# Amplificador_Clase_D.net
KiCad netlist of a schematic drawn in Altium Designer
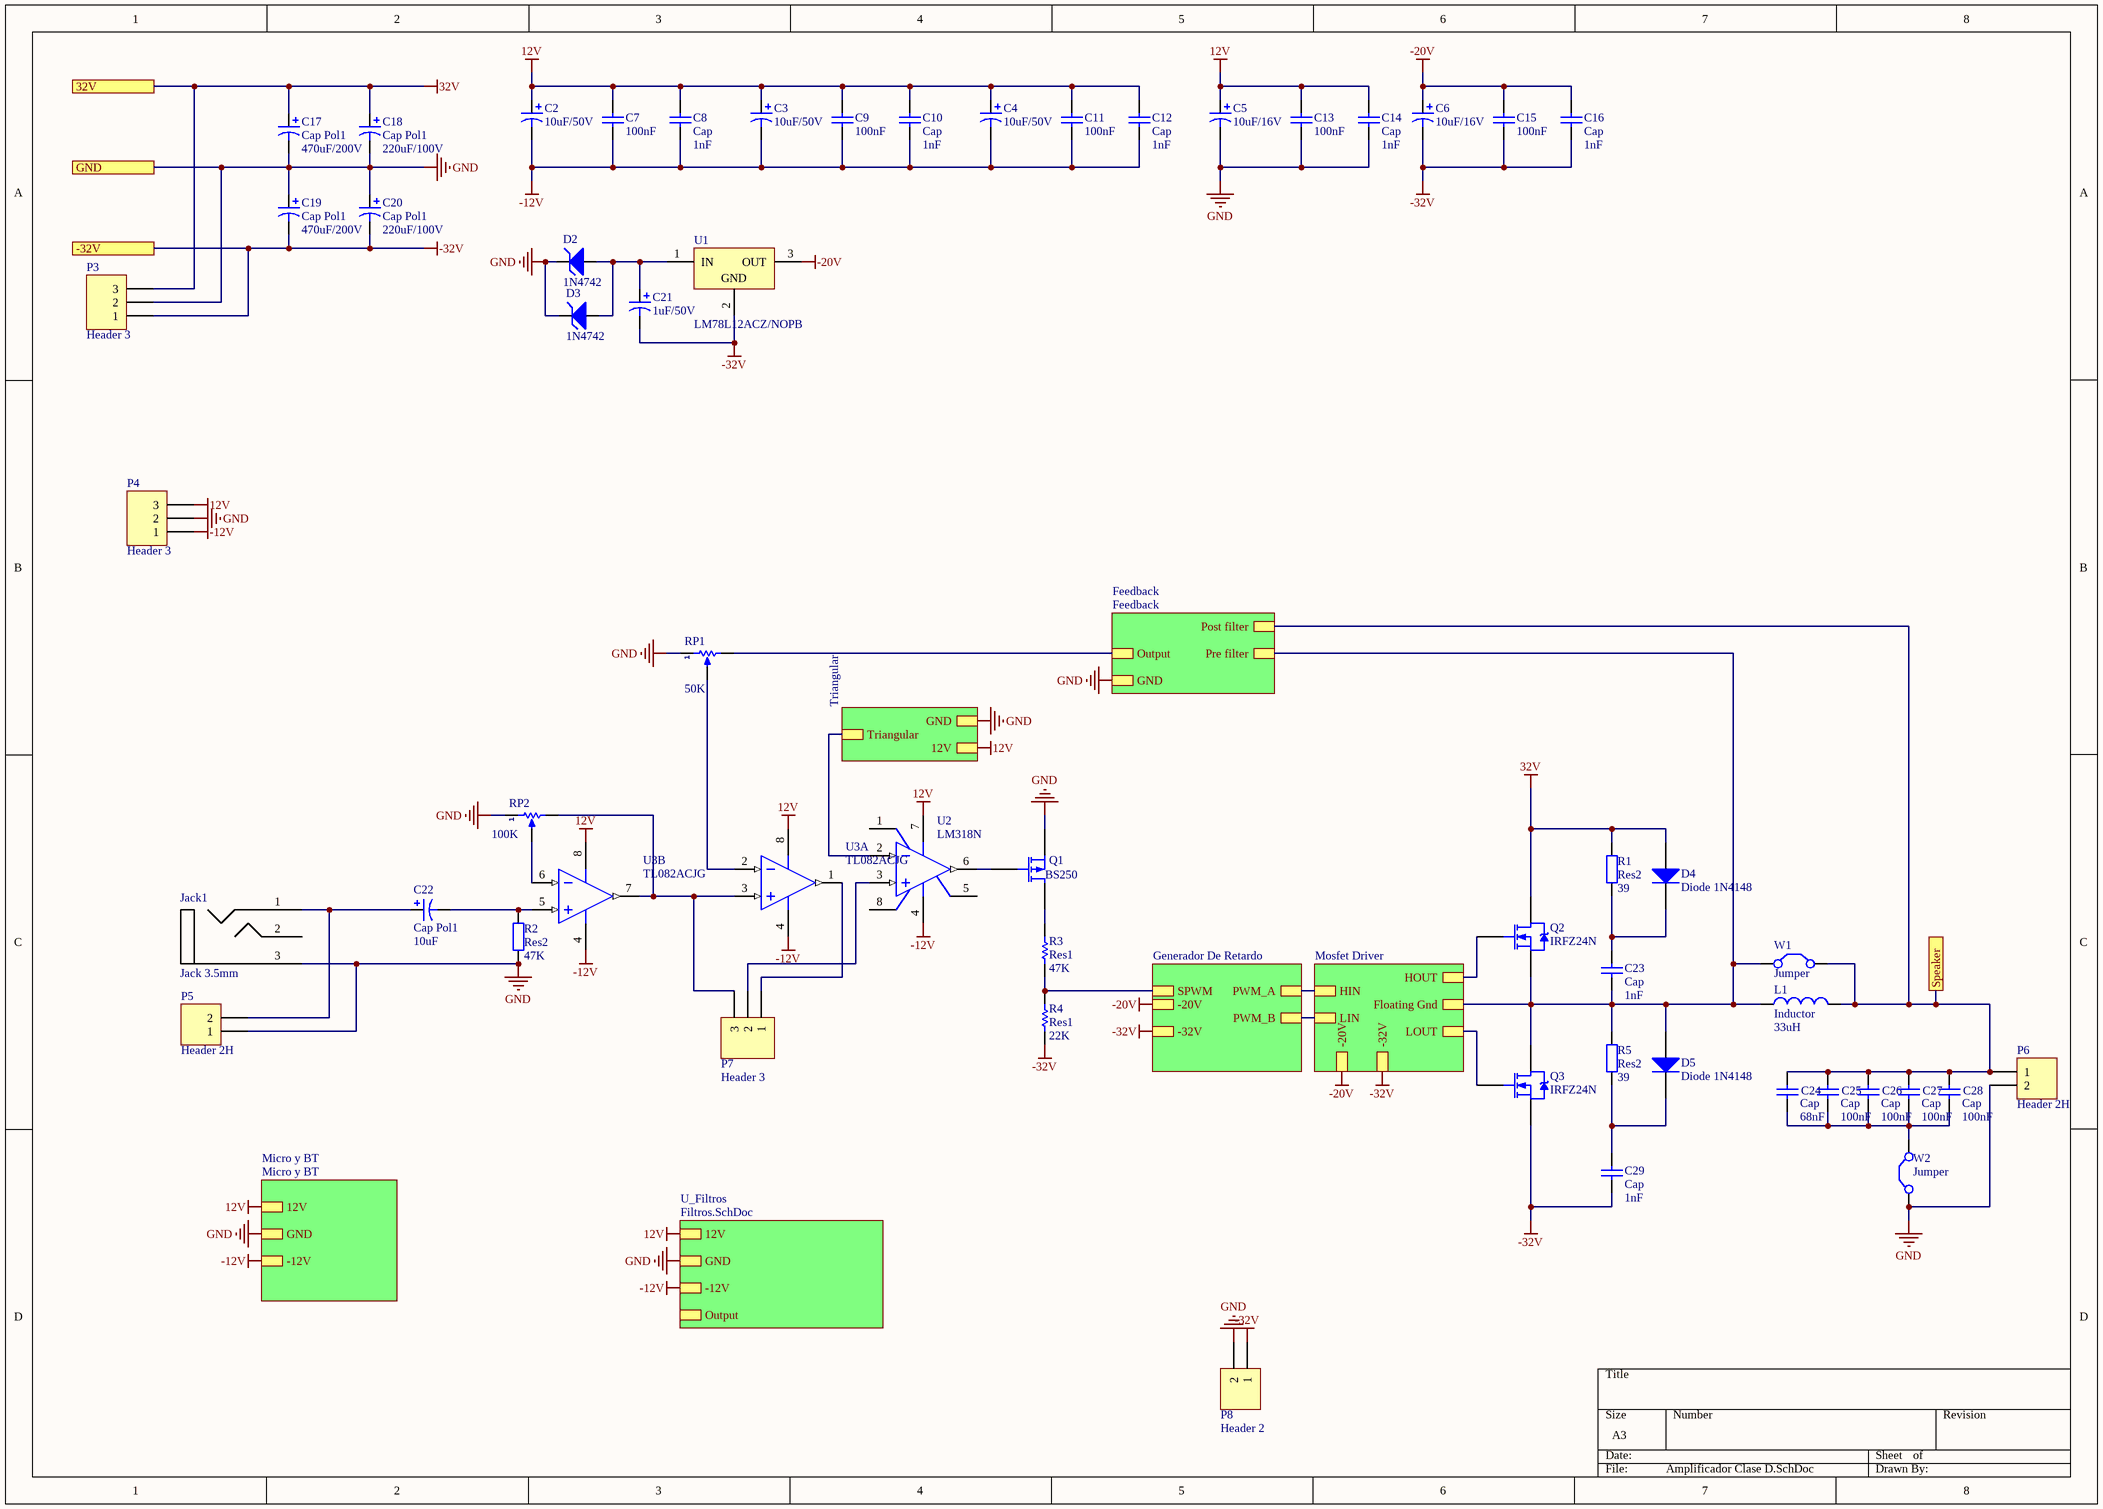
[diagram p0: Amplificador Clase D.SchDoc]

(export (version "E")
  (design (tool "Eeschema 10.0.6"))
  (components
    (comp (ref "C2")
      (value "Cap Electrolitico Radial")
      (footprint "CAPR D250 H450 R100 mil")
      (description "Cap Electrolitico de insercion")
      (fields (field (name "VALOR") "10uF/50V"))
      (libsource (lib "RUF-Dispositivos-Grales") (part "Cap Electrolitico Radial"))
    )
    (comp (ref "C3")
      (value "Cap Electrolitico Radial")
      (footprint "CAPR D250 H450 R100 mil")
      (description "Cap Electrolitico de insercion")
      (fields (field (name "VALOR") "10uF/50V"))
      (libsource (lib "RUF-Dispositivos-Grales") (part "Cap Electrolitico Radial"))
    )
    (comp (ref "C4")
      (value "Cap Electrolitico Radial")
      (footprint "CAPR D250 H450 R100 mil")
      (description "Cap Electrolitico de insercion")
      (fields (field (name "VALOR") "10uF/50V"))
      (libsource (lib "RUF-Dispositivos-Grales") (part "Cap Electrolitico Radial"))
    )
    (comp (ref "C5")
      (value "Cap Electrolitico Radial")
      (footprint "CAPR D250 H450 R100 mil")
      (description "Cap Electrolitico de insercion")
      (fields (field (name "VALOR") "10uF/16V"))
      (libsource (lib "RUF-Dispositivos-Grales") (part "Cap Electrolitico Radial"))
    )
    (comp (ref "C6")
      (value "Cap Electrolitico Radial")
      (footprint "CAPR D250 H450 R100 mil")
      (description "Cap Electrolitico de insercion")
      (fields (field (name "VALOR") "10uF/16V"))
      (libsource (lib "RUF-Dispositivos-Grales") (part "Cap Electrolitico Radial"))
    )
    (comp (ref "C7")
      (value "Cap Ceramico Disco")
      (footprint "RAD-0.3")
      (description "Capacitor Ceramico de Insercion")
      (fields (field (name "VALOR") "100nF"))
      (libsource (lib "RUF-Dispositivos-Grales") (part "Cap Ceramico Disco"))
    )
    (comp (ref "C8")
      (value "Cap")
      (footprint "CAP DISCO 200mil")
      (description "Capacitor")
      (fields (field (name "ALTIUM_VALUE") "1nF") (field (name "PUBLISHER") "Altium Limited"))
      (libsource (lib "Miscellaneous Devices") (part "Cap"))
    )
    (comp (ref "C9")
      (value "Cap Ceramico Disco")
      (footprint "RAD-0.3")
      (description "Capacitor Ceramico de Insercion")
      (fields (field (name "VALOR") "100nF"))
      (libsource (lib "RUF-Dispositivos-Grales") (part "Cap Ceramico Disco"))
    )
    (comp (ref "C10")
      (value "Cap")
      (footprint "CAP DISCO 200mil")
      (description "Capacitor")
      (fields (field (name "ALTIUM_VALUE") "1nF") (field (name "PUBLISHER") "Altium Limited"))
      (libsource (lib "Miscellaneous Devices") (part "Cap"))
    )
    (comp (ref "C11")
      (value "Cap Ceramico Disco")
      (footprint "RAD-0.3")
      (description "Capacitor Ceramico de Insercion")
      (fields (field (name "VALOR") "100nF"))
      (libsource (lib "RUF-Dispositivos-Grales") (part "Cap Ceramico Disco"))
    )
    (comp (ref "C12")
      (value "Cap")
      (footprint "CAP DISCO 200mil")
      (description "Capacitor")
      (fields (field (name "ALTIUM_VALUE") "1nF") (field (name "PUBLISHER") "Altium Limited"))
      (libsource (lib "Miscellaneous Devices") (part "Cap"))
    )
    (comp (ref "C13")
      (value "Cap Ceramico Disco")
      (footprint "RAD-0.3")
      (description "Capacitor Ceramico de Insercion")
      (fields (field (name "VALOR") "100nF"))
      (libsource (lib "RUF-Dispositivos-Grales") (part "Cap Ceramico Disco"))
    )
    (comp (ref "C14")
      (value "Cap")
      (footprint "CAP DISCO 200mil")
      (description "Capacitor")
      (fields (field (name "ALTIUM_VALUE") "1nF") (field (name "PUBLISHER") "Altium Limited"))
      (libsource (lib "Miscellaneous Devices") (part "Cap"))
    )
    (comp (ref "C15")
      (value "Cap Ceramico Disco")
      (footprint "RAD-0.3")
      (description "Capacitor Ceramico de Insercion")
      (fields (field (name "VALOR") "100nF"))
      (libsource (lib "RUF-Dispositivos-Grales") (part "Cap Ceramico Disco"))
    )
    (comp (ref "C16")
      (value "Cap")
      (footprint "CAP DISCO 200mil")
      (description "Capacitor")
      (fields (field (name "ALTIUM_VALUE") "1nF") (field (name "PUBLISHER") "Altium Limited"))
      (libsource (lib "Miscellaneous Devices") (part "Cap"))
    )
    (comp (ref "C17")
      (value "Cap Pol1")
      (footprint "CAPR D700 H1400 R300 mil")
      (description "Polarized Capacitor (Radial)")
      (fields (field (name "ALTIUM_VALUE") "470uF/200V") (field (name "PUBLISHER") "Altium Limited"))
      (libsource (lib "Miscellaneous Devices") (part "Cap Pol1"))
    )
    (comp (ref "C18")
      (value "Cap Pol1")
      (footprint "CAPR D500 H1000 R200 mil")
      (description "Polarized Capacitor (Radial)")
      (fields (field (name "ALTIUM_VALUE") "220uF/100V") (field (name "PUBLISHER") "Altium Limited"))
      (libsource (lib "Miscellaneous Devices") (part "Cap Pol1"))
    )
    (comp (ref "C19")
      (value "Cap Pol1")
      (footprint "CAPR D700 H1400 R300 mil")
      (description "Polarized Capacitor (Radial)")
      (fields (field (name "ALTIUM_VALUE") "470uF/200V") (field (name "PUBLISHER") "Altium Limited"))
      (libsource (lib "Miscellaneous Devices") (part "Cap Pol1"))
    )
    (comp (ref "C20")
      (value "Cap Pol1")
      (footprint "CAPR D500 H1000 R200 mil")
      (description "Polarized Capacitor (Radial)")
      (fields (field (name "ALTIUM_VALUE") "220uF/100V") (field (name "PUBLISHER") "Altium Limited"))
      (libsource (lib "Miscellaneous Devices") (part "Cap Pol1"))
    )
    (comp (ref "C21")
      (value "Cap Electrolitico Radial")
      (footprint "CAPR D250 H450 R100 mil")
      (description "Cap Electrolitico de insercion")
      (fields (field (name "VALOR") "1uF/50V"))
      (libsource (lib "RUF-Dispositivos-Grales") (part "Cap Electrolitico Radial"))
    )
    (comp (ref "C22")
      (value "Cap Pol1")
      (footprint "CAPR D250 H450 R100 mil")
      (description "Polarized Capacitor (Radial)")
      (fields (field (name "ALTIUM_VALUE") "10uF") (field (name "PUBLISHER") "Altium Limited"))
      (libsource (lib "Miscellaneous Devices") (part "Cap Pol1"))
    )
    (comp (ref "C23")
      (value "Cap")
      (footprint "CAP DISCO 200mil")
      (description "Capacitor")
      (fields (field (name "ALTIUM_VALUE") "1nF") (field (name "PUBLISHER") "Altium Limited"))
      (libsource (lib "Miscellaneous Devices") (part "Cap"))
    )
    (comp (ref "C24")
      (value "Cap")
      (footprint "RAD-0.4")
      (description "Capacitor")
      (fields (field (name "ALTIUM_VALUE") "68nF") (field (name "PUBLISHER") "Altium Limited"))
      (libsource (lib "Miscellaneous Devices") (part "Cap"))
    )
    (comp (ref "C25")
      (value "Cap")
      (footprint "RAD-0.4")
      (description "Capacitor")
      (fields (field (name "ALTIUM_VALUE") "100nF") (field (name "PUBLISHER") "Altium Limited"))
      (libsource (lib "Miscellaneous Devices") (part "Cap"))
    )
    (comp (ref "C26")
      (value "Cap")
      (footprint "RAD-0.4")
      (description "Capacitor")
      (fields (field (name "ALTIUM_VALUE") "100nF") (field (name "PUBLISHER") "Altium Limited"))
      (libsource (lib "Miscellaneous Devices") (part "Cap"))
    )
    (comp (ref "C27")
      (value "Cap")
      (footprint "RAD-0.4")
      (description "Capacitor")
      (fields (field (name "ALTIUM_VALUE") "100nF") (field (name "PUBLISHER") "Altium Limited"))
      (libsource (lib "Miscellaneous Devices") (part "Cap"))
    )
    (comp (ref "C28")
      (value "Cap")
      (footprint "RAD-0.4")
      (description "Capacitor")
      (fields (field (name "ALTIUM_VALUE") "100nF") (field (name "PUBLISHER") "Altium Limited"))
      (libsource (lib "Miscellaneous Devices") (part "Cap"))
    )
    (comp (ref "C29")
      (value "Cap")
      (footprint "CAP DISCO 200mil")
      (description "Capacitor")
      (fields (field (name "ALTIUM_VALUE") "1nF") (field (name "PUBLISHER") "Altium Limited"))
      (libsource (lib "Miscellaneous Devices") (part "Cap"))
    )
    (comp (ref "D2")
      (value "Diodo Zener")
      (footprint "DO-41")
      (fields (field (name "VALOR") "1N4742"))
      (libsource (lib "RUF-Dispositivos-Grales") (part "Diodo Zener"))
    )
    (comp (ref "D3")
      (value "Diodo Zener")
      (footprint "DO-41")
      (fields (field (name "VALOR") "1N4742"))
      (libsource (lib "RUF-Dispositivos-Grales") (part "Diodo Zener"))
    )
    (comp (ref "D4")
      (value "Diode 1N4148")
      (footprint "DO-41")
      (description "High Conductance Fast Diode")
      (fields (field (name "PUBLISHER") "Altium Limited"))
      (libsource (lib "Miscellaneous Devices") (part "Diode 1N4148"))
    )
    (comp (ref "D5")
      (value "Diode 1N4148")
      (footprint "DO-41")
      (description "High Conductance Fast Diode")
      (fields (field (name "PUBLISHER") "Altium Limited"))
      (libsource (lib "Miscellaneous Devices") (part "Diode 1N4148"))
    )
    (comp (ref "Jack1")
      (value "Jack 3.5mm")
      (footprint "jack 3.5mm")
      (libsource (lib "XR2206") (part "Jack 3.5mm"))
    )
    (comp (ref "L1")
      (value "Inductor")
      (footprint "Bobina 1.5*3")
      (fields (field (name "ALTIUM_VALUE") "33uH") (field (name "PUBLISHER") "Altium Limited"))
      (libsource (lib "Miscellaneous Devices") (part "Inductor"))
    )
    (comp (ref "P3")
      (value "Header 3")
      (footprint "bornera 3")
      (description "Header, 3-Pin")
      (fields (field (name "PUBLISHER") "Altium Limited"))
      (libsource (lib "Miscellaneous Connectors") (part "Header 3"))
    )
    (comp (ref "P4")
      (value "Header 3")
      (footprint "bornera 3")
      (description "Header, 3-Pin")
      (fields (field (name "PUBLISHER") "Altium Limited"))
      (libsource (lib "Miscellaneous Connectors") (part "Header 3"))
    )
    (comp (ref "P5")
      (value "Header 2H")
      (footprint "bornera 2")
      (description "Header, 2-Pin, Right Angle")
      (fields (field (name "PUBLISHER") "Altium Limited"))
      (libsource (lib "") (part "Header 2H_1"))
    )
    (comp (ref "P6")
      (value "Header 2H")
      (footprint "bornera 2")
      (description "Header, 2-Pin, Right Angle")
      (fields (field (name "PUBLISHER") "Altium Limited"))
      (libsource (lib "Miscellaneous Connectors") (part "Header 2H"))
    )
    (comp (ref "P7")
      (value "Header 3")
      (footprint "HDR1X3")
      (description "Header, 3-Pin")
      (fields (field (name "PUBLISHER") "Altium Limited"))
      (libsource (lib "") (part "Header 3_1"))
    )
    (comp (ref "P8")
      (value "Header 2")
      (footprint "HDR1X2")
      (description "Header, 2-Pin")
      (fields (field (name "PUBLISHER") "Altium Limited"))
      (libsource (lib "Miscellaneous Connectors") (part "Header 2"))
    )
    (comp (ref "Q1")
      (value "BS250")
      (footprint "TO-92W")
      (description "P-Channel MOSFET")
      (fields (field (name "PUBLISHER") "Altium Limited"))
      (libsource (lib "Miscellaneous Devices") (part "MOSFET-P"))
    )
    (comp (ref "Q2")
      (value "IRFZ24N")
      (footprint "TO-220AB")
      (description "HEXFET Power MOSFET")
      (fields (field (name "PUBLISHER") "Altium Limited"))
      (libsource (lib "IR Discrete MOSFET - Power") (part "IRFZ24N"))
    )
    (comp (ref "Q3")
      (value "IRFZ24N")
      (footprint "TO-220AB")
      (description "HEXFET Power MOSFET")
      (fields (field (name "PUBLISHER") "Altium Limited"))
      (libsource (lib "IR Discrete MOSFET - Power") (part "IRFZ24N"))
    )
    (comp (ref "R1")
      (value "Res2")
      (footprint "AXIAL-0.4")
      (description "Resistor")
      (fields (field (name "ALTIUM_VALUE") "39") (field (name "PUBLISHER") "Altium Limited"))
      (libsource (lib "Miscellaneous Devices") (part "Res2"))
    )
    (comp (ref "R2")
      (value "Res2")
      (footprint "1206 resistor")
      (description "Resistor")
      (fields (field (name "ALTIUM_VALUE") "47K") (field (name "PUBLISHER") "Altium Limited"))
      (libsource (lib "Miscellaneous Devices") (part "Res2"))
    )
    (comp (ref "R3")
      (value "Res1")
      (footprint "1206 resistor")
      (description "Resistor")
      (fields (field (name "ALTIUM_VALUE") "47K") (field (name "PUBLISHER") "Altium Limited"))
      (libsource (lib "Miscellaneous Devices") (part "Res1"))
    )
    (comp (ref "R4")
      (value "Res1")
      (footprint "1206 resistor")
      (description "Resistor")
      (fields (field (name "ALTIUM_VALUE") "22K") (field (name "PUBLISHER") "Altium Limited"))
      (libsource (lib "Miscellaneous Devices") (part "Res1"))
    )
    (comp (ref "R5")
      (value "Res2")
      (footprint "AXIAL-0.4")
      (description "Resistor")
      (fields (field (name "ALTIUM_VALUE") "39") (field (name "PUBLISHER") "Altium Limited"))
      (libsource (lib "Miscellaneous Devices") (part "Res2"))
    )
    (comp (ref "RP1")
      (value "Trimpot")
      (footprint "Trimpot Multivuelta Vertical")
      (description "Preset")
      (fields (field (name "VALOR") "50K"))
      (libsource (lib "RUF-Dispositivos-Grales") (part "Trimpot"))
    )
    (comp (ref "RP2")
      (value "Trimpot")
      (footprint "Trimpot Multivuelta Vertical")
      (description "Preset")
      (fields (field (name "VALOR") "100K"))
      (libsource (lib "RUF-Dispositivos-Grales") (part "Trimpot"))
    )
    (comp (ref "U1")
      (value "LM78L12ACZ/NOPB")
      (footprint "to-220")
      (description "3-Terminal Positive Regulators, 3-pin TO-92, Pb-Free")
      (fields
        (field (name "MANUFACTURER") "National Semiconductor")
        (field (name "PUBLISHER") "Altium Limited")
      )
      (libsource (lib "NSC LDO") (part "LM78L12ACZ/NOPB"))
    )
    (comp (ref "U2")
      (value "LM318N")
      (footprint "DIP-8")
      (description "Operational Amplifier, 8-pin MDIP")
      (fields
        (field (name "MANUFACTURER") "National Semiconductor")
        (field (name "PUBLISHER") "Altium Limited")
      )
      (libsource (lib "NSC Amplifier") (part "LM318N"))
    )
    (comp (ref "U3")
      (value "TL082ACJG")
      (footprint "693-02")
      (description "JFET-Input Operational Amplifier")
      (fields (field (name "PUBLISHER") "Altium Limited"))
      (libsource (lib "Motorola Amplifier Operational Amplifier") (part "TL082ACJG"))
    )
    (comp (ref "W1")
      (value "Jumper")
      (footprint "RAD-0.2")
      (description "Jumper Wire")
      (fields (field (name "PUBLISHER") "Altium Limited"))
      (libsource (lib "Miscellaneous Devices") (part "Jumper"))
    )
    (comp (ref "W2")
      (value "Jumper")
      (footprint "RAD-0.2")
      (description "Jumper Wire")
      (fields (field (name "PUBLISHER") "Altium Limited"))
      (libsource (lib "Miscellaneous Devices") (part "Jumper"))
    )
  )
  (nets
    (net (code "1") (name "-12V") (class "Default")
      (node (ref "C10") (pin "1") (pinfunction "1_1") (pintype "passive"))
      (node (ref "C11") (pin "1") (pinfunction "1_1") (pintype "passive"))
      (node (ref "C12") (pin "1") (pinfunction "1_1") (pintype "passive"))
      (node (ref "C2") (pin "2") (pinfunction "2_2") (pintype "passive"))
      (node (ref "C3") (pin "2") (pinfunction "2_2") (pintype "passive"))
      (node (ref "C4") (pin "2") (pinfunction "2_2") (pintype "passive"))
      (node (ref "C7") (pin "1") (pinfunction "1_1") (pintype "passive"))
      (node (ref "C8") (pin "1") (pinfunction "1_1") (pintype "passive"))
      (node (ref "C9") (pin "1") (pinfunction "1_1") (pintype "passive"))
      (node (ref "P4") (pin "1") (pinfunction "1_1") (pintype "passive"))
      (node (ref "U2") (pin "4") (pinfunction "V-_4") (pintype "power_in"))
      (node (ref "U3") (pin "4") (pinfunction "V-_4") (pintype "power_in"))
    )
    (net (code "2") (name "-20V") (class "Default")
      (node (ref "C15") (pin "2") (pinfunction "2_2") (pintype "passive"))
      (node (ref "C16") (pin "2") (pinfunction "2_2") (pintype "passive"))
      (node (ref "C6") (pin "1") (pinfunction "1_1") (pintype "passive"))
      (node (ref "U1") (pin "3") (pinfunction "OUT_3") (pintype "power_in"))
    )
    (net (code "3") (name "-32V") (class "Default")
      (node (ref "C15") (pin "1") (pinfunction "1_1") (pintype "passive"))
      (node (ref "C16") (pin "1") (pinfunction "1_1") (pintype "passive"))
      (node (ref "C19") (pin "2") (pinfunction "2_2") (pintype "passive"))
      (node (ref "C20") (pin "2") (pinfunction "2_2") (pintype "passive"))
      (node (ref "C21") (pin "2") (pinfunction "2_2") (pintype "passive"))
      (node (ref "C29") (pin "1") (pinfunction "1_1") (pintype "passive"))
      (node (ref "C6") (pin "2") (pinfunction "2_2") (pintype "passive"))
      (node (ref "P3") (pin "1") (pinfunction "1_1") (pintype "passive"))
      (node (ref "P8") (pin "1") (pinfunction "1_1") (pintype "passive"))
      (node (ref "Q3") (pin "3") (pinfunction "S_3") (pintype "passive"))
      (node (ref "R4") (pin "1") (pinfunction "1_1") (pintype "passive"))
      (node (ref "U1") (pin "2") (pinfunction "GND_2") (pintype "power_in"))
    )
    (net (code "4") (name "/Floating Gnd") (class "Default")
      (node (ref "C23") (pin "1") (pinfunction "1_1") (pintype "passive"))
      (node (ref "D5") (pin "1") (pinfunction "A_1") (pintype "passive"))
      (node (ref "L1") (pin "1") (pinfunction "1_1") (pintype "passive"))
      (node (ref "Q2") (pin "3") (pinfunction "S_3") (pintype "passive"))
      (node (ref "Q3") (pin "2") (pinfunction "D_2") (pintype "passive"))
      (node (ref "R5") (pin "2") (pinfunction "2_2") (pintype "passive"))
      (node (ref "W1") (pin "1") (pinfunction "C1_1") (pintype "passive"))
    )
    (net (code "6") (name "/HOUT") (class "Default")
      (node (ref "Q2") (pin "1") (pinfunction "G_1") (pintype "passive"))
    )
    (net (code "8") (name "/LOUT") (class "Default")
      (node (ref "Q3") (pin "1") (pinfunction "G_1") (pintype "passive"))
    )
    (net (code "10") (name "/Output_1") (class "Default")
      (node (ref "RP1") (pin "2") (pinfunction "BOT_2") (pintype "passive"))
    )
    (net (code "11") (name "/SPWM") (class "Default")
      (node (ref "R3") (pin "1") (pinfunction "1_1") (pintype "passive"))
      (node (ref "R4") (pin "2") (pinfunction "2_2") (pintype "passive"))
    )
    (net (code "12") (name "/Speaker") (class "Default")
      (node (ref "C24") (pin "2") (pinfunction "2_2") (pintype "passive"))
      (node (ref "C25") (pin "2") (pinfunction "2_2") (pintype "passive"))
      (node (ref "C26") (pin "2") (pinfunction "2_2") (pintype "passive"))
      (node (ref "C27") (pin "2") (pinfunction "2_2") (pintype "passive"))
      (node (ref "C28") (pin "2") (pinfunction "2_2") (pintype "passive"))
      (node (ref "L1") (pin "2") (pinfunction "2_2") (pintype "passive"))
      (node (ref "P6") (pin "1") (pinfunction "1_1") (pintype "passive"))
      (node (ref "W1") (pin "2") (pinfunction "C2_2") (pintype "passive"))
    )
    (net (code "13") (name "/Triangular") (class "Default")
      (node (ref "U2") (pin "2") (pinfunction "IN-_2") (pintype "input"))
    )
    (net (code "14") (name "12V") (class "Default")
      (node (ref "C10") (pin "2") (pinfunction "2_2") (pintype "passive"))
      (node (ref "C11") (pin "2") (pinfunction "2_2") (pintype "passive"))
      (node (ref "C12") (pin "2") (pinfunction "2_2") (pintype "passive"))
      (node (ref "C13") (pin "2") (pinfunction "2_2") (pintype "passive"))
      (node (ref "C14") (pin "2") (pinfunction "2_2") (pintype "passive"))
      (node (ref "C2") (pin "1") (pinfunction "1_1") (pintype "passive"))
      (node (ref "C3") (pin "1") (pinfunction "1_1") (pintype "passive"))
      (node (ref "C4") (pin "1") (pinfunction "1_1") (pintype "passive"))
      (node (ref "C5") (pin "1") (pinfunction "1_1") (pintype "passive"))
      (node (ref "C7") (pin "2") (pinfunction "2_2") (pintype "passive"))
      (node (ref "C8") (pin "2") (pinfunction "2_2") (pintype "passive"))
      (node (ref "C9") (pin "2") (pinfunction "2_2") (pintype "passive"))
      (node (ref "P4") (pin "3") (pinfunction "3_3") (pintype "passive"))
      (node (ref "U2") (pin "7") (pinfunction "V+_7") (pintype "power_in"))
      (node (ref "U3") (pin "8") (pinfunction "V+_8") (pintype "power_in"))
    )
    (net (code "15") (name "32V") (class "Default")
      (node (ref "C17") (pin "1") (pinfunction "1_1") (pintype "passive"))
      (node (ref "C18") (pin "1") (pinfunction "1_1") (pintype "passive"))
      (node (ref "D4") (pin "1") (pinfunction "A_1") (pintype "passive"))
      (node (ref "P3") (pin "3") (pinfunction "3_3") (pintype "passive"))
      (node (ref "Q2") (pin "2") (pinfunction "D_2") (pintype "passive"))
      (node (ref "R1") (pin "2") (pinfunction "2_2") (pintype "passive"))
    )
    (net (code "16") (name "GND") (class "Default")
      (node (ref "C13") (pin "1") (pinfunction "1_1") (pintype "passive"))
      (node (ref "C14") (pin "1") (pinfunction "1_1") (pintype "passive"))
      (node (ref "C17") (pin "2") (pinfunction "2_2") (pintype "passive"))
      (node (ref "C18") (pin "2") (pinfunction "2_2") (pintype "passive"))
      (node (ref "C19") (pin "1") (pinfunction "1_1") (pintype "passive"))
      (node (ref "C20") (pin "1") (pinfunction "1_1") (pintype "passive"))
      (node (ref "C5") (pin "2") (pinfunction "2_2") (pintype "passive"))
      (node (ref "D2") (pin "2") (pinfunction "K_2") (pintype "passive"))
      (node (ref "D3") (pin "2") (pinfunction "K_2") (pintype "passive"))
      (node (ref "Jack1") (pin "3") (pinfunction "Gnd_3") (pintype "passive"))
      (node (ref "P3") (pin "2") (pinfunction "2_2") (pintype "passive"))
      (node (ref "P4") (pin "2") (pinfunction "2_2") (pintype "passive"))
      (node (ref "P5") (pin "1") (pinfunction "1_1") (pintype "passive"))
      (node (ref "P6") (pin "2") (pinfunction "2_2") (pintype "passive"))
      (node (ref "P8") (pin "2") (pinfunction "2_2") (pintype "passive"))
      (node (ref "Q1") (pin "3") (pinfunction "S_3") (pintype "passive"))
      (node (ref "R2") (pin "1") (pinfunction "1_1") (pintype "passive"))
      (node (ref "RP1") (pin "1") (pinfunction "TOP_1") (pintype "passive"))
      (node (ref "RP2") (pin "1") (pinfunction "TOP_1") (pintype "passive"))
      (node (ref "W2") (pin "1") (pinfunction "C1_1") (pintype "passive"))
    )
    (net (code "17") (name "Net-(D2-A)") (class "Default")
      (node (ref "C21") (pin "1") (pinfunction "1_1") (pintype "passive"))
      (node (ref "D2") (pin "1") (pinfunction "A_1") (pintype "passive"))
      (node (ref "D3") (pin "1") (pinfunction "A_1") (pintype "passive"))
      (node (ref "U1") (pin "1") (pinfunction "IN_1") (pintype "power_in"))
    )
    (net (code "18") (name "Net-(D4-K)") (class "Default")
      (node (ref "C23") (pin "2") (pinfunction "2_2") (pintype "passive"))
      (node (ref "D4") (pin "2") (pinfunction "K_2") (pintype "passive"))
      (node (ref "R1") (pin "1") (pinfunction "1_1") (pintype "passive"))
    )
    (net (code "19") (name "Net-(D5-K)") (class "Default")
      (node (ref "C29") (pin "2") (pinfunction "2_2") (pintype "passive"))
      (node (ref "D5") (pin "2") (pinfunction "K_2") (pintype "passive"))
      (node (ref "R5") (pin "1") (pinfunction "1_1") (pintype "passive"))
    )
    (net (code "20") (name "Net-(Jack1-R)") (class "Default")
      (node (ref "C22") (pin "1") (pinfunction "1_1") (pintype "passive"))
      (node (ref "Jack1") (pin "1") (pinfunction "R_1") (pintype "passive"))
      (node (ref "P5") (pin "2") (pinfunction "2_2") (pintype "passive"))
    )
    (net (code "21") (name "Net-(Q1-D)") (class "Default")
      (node (ref "Q1") (pin "1") (pinfunction "D_1") (pintype "passive"))
      (node (ref "R3") (pin "2") (pinfunction "2_2") (pintype "passive"))
    )
    (net (code "22") (name "Net-(Q1-G)") (class "Default")
      (node (ref "Q1") (pin "2") (pinfunction "G_2") (pintype "passive"))
      (node (ref "U2") (pin "6") (pinfunction "OUT_6") (pintype "output"))
    )
    (net (code "23") (name "Net-(RP1-TAP)") (class "Default")
      (node (ref "RP1") (pin "3") (pinfunction "TAP_3") (pintype "passive"))
      (node (ref "U3") (pin "2") (pinfunction "IN-_2") (pintype "input"))
    )
    (net (code "24") (name "Net-(RP2-BOT)") (class "Default")
      (node (ref "P7") (pin "3") (pinfunction "3_3") (pintype "passive"))
      (node (ref "RP2") (pin "2") (pinfunction "BOT_2") (pintype "passive"))
      (node (ref "U3") (pin "3") (pinfunction "IN+_3") (pintype "input"))
      (node (ref "U3") (pin "7") (pinfunction "OUT_7") (pintype "output"))
    )
    (net (code "25") (name "Net-(RP2-TAP)") (class "Default")
      (node (ref "RP2") (pin "3") (pinfunction "TAP_3") (pintype "passive"))
      (node (ref "U3") (pin "6") (pinfunction "IN-_6") (pintype "input"))
    )
    (net (code "26") (name "Net-(U2-IN+)") (class "Default")
      (node (ref "P7") (pin "2") (pinfunction "2_2") (pintype "passive"))
      (node (ref "U2") (pin "3") (pinfunction "IN+_3") (pintype "input"))
    )
    (net (code "27") (name "Net-(U3A-OUT)") (class "Default")
      (node (ref "P7") (pin "1") (pinfunction "1_1") (pintype "passive"))
      (node (ref "U3") (pin "1") (pinfunction "OUT_1") (pintype "output"))
    )
    (net (code "28") (name "Net-(U3B-IN+)") (class "Default")
      (node (ref "C22") (pin "2") (pinfunction "2_2") (pintype "passive"))
      (node (ref "R2") (pin "2") (pinfunction "2_2") (pintype "passive"))
      (node (ref "U3") (pin "5") (pinfunction "IN+_5") (pintype "input"))
    )
    (net (code "29") (name "Net-(W2-C2)") (class "Default")
      (node (ref "C24") (pin "1") (pinfunction "1_1") (pintype "passive"))
      (node (ref "C25") (pin "1") (pinfunction "1_1") (pintype "passive"))
      (node (ref "C26") (pin "1") (pinfunction "1_1") (pintype "passive"))
      (node (ref "C27") (pin "1") (pinfunction "1_1") (pintype "passive"))
      (node (ref "C28") (pin "1") (pinfunction "1_1") (pintype "passive"))
      (node (ref "W2") (pin "2") (pinfunction "C2_2") (pintype "passive"))
    )
    (net (code "30") (name "unconnected-(Jack1-L-Pad2)") (class "Default")
      (node (ref "Jack1") (pin "2") (pinfunction "L_2") (pintype "passive"))
    )
    (net (code "31") (name "unconnected-(U2-BAL{slash}COMP1-Pad1)") (class "Default")
      (node (ref "U2") (pin "1") (pinfunction "BAL/COMP1_1") (pintype "passive"))
    )
    (net (code "32") (name "unconnected-(U2-BAL{slash}COMP3-Pad5)") (class "Default")
      (node (ref "U2") (pin "5") (pinfunction "BAL/COMP3_5") (pintype "passive"))
    )
    (net (code "33") (name "unconnected-(U2-COMP2-Pad8)") (class "Default")
      (node (ref "U2") (pin "8") (pinfunction "COMP2_8") (pintype "passive"))
    )
  )
)
